# Powersupply.net
KiCad netlist of a schematic drawn in Altium Designer
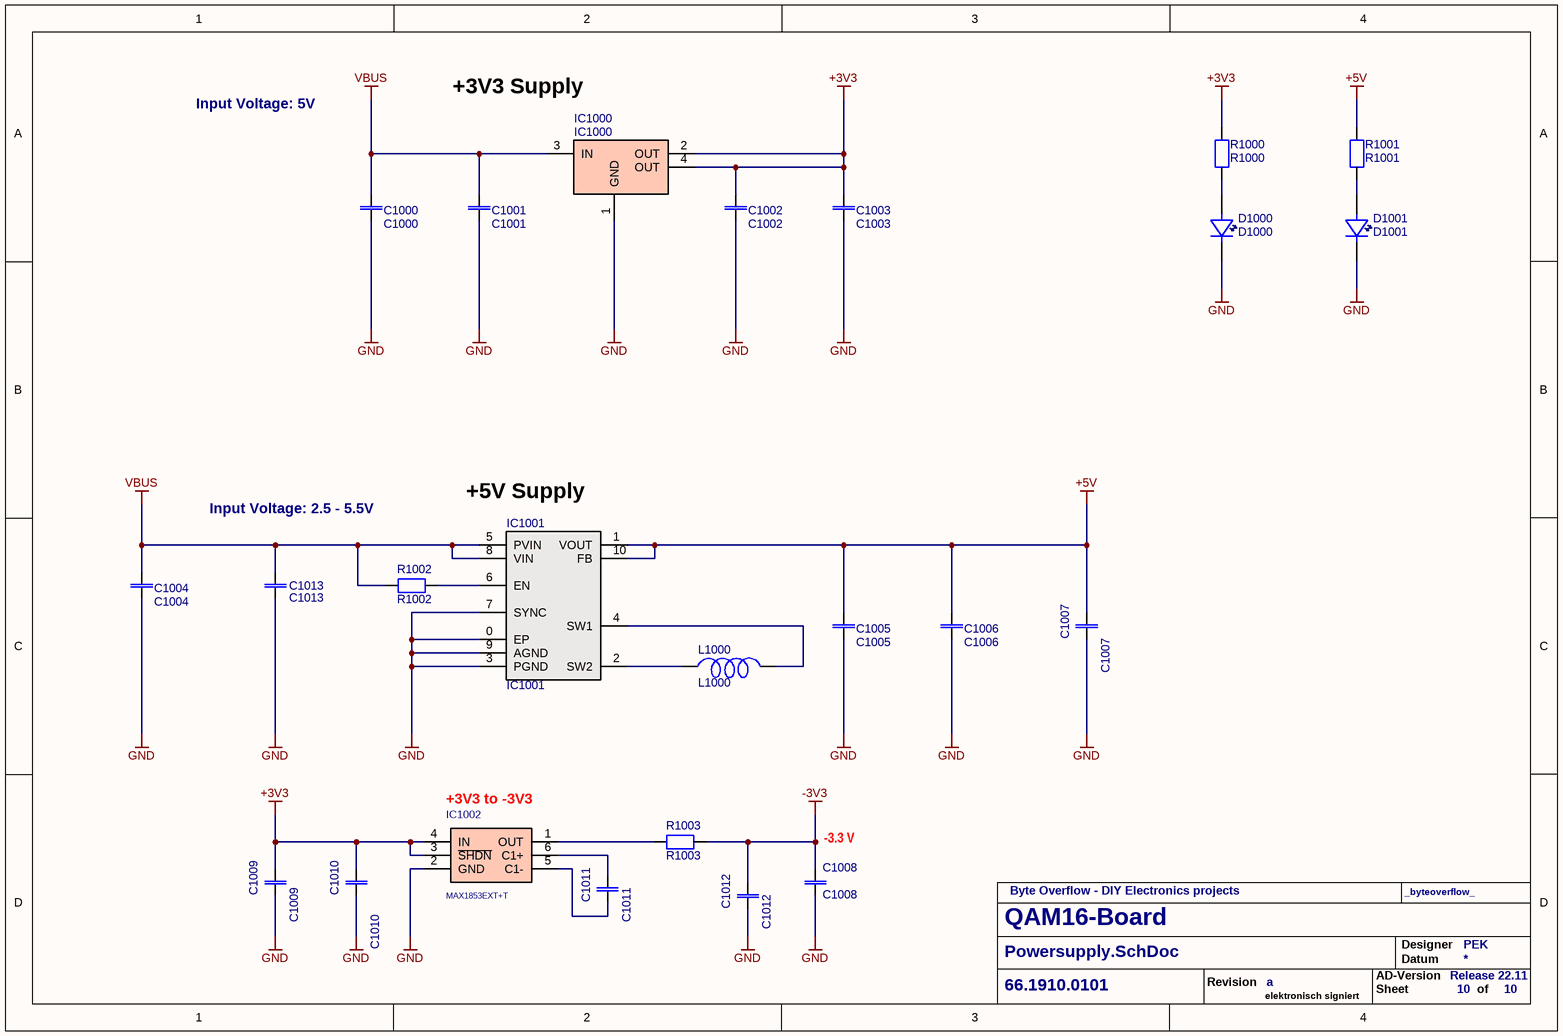
[diagram p0: Powersupply.SchDoc]

(export (version "E")
  (design (tool "Eeschema 10.0.6"))
  (components
    (comp (ref "C1000")
      (value "C 1uF 50V")
      (footprint "0805-2012")
      (description "Capacitor")
      (fields
        (field (name "MANUFACTURER") "Murata Electronics North America")
        (field (name "MANUFACTURER PART NUMBER") "GRM21BF51H105ZA12L")
      )
      (libsource (lib "Database_Libs1") (part "Kondensator"))
    )
    (comp (ref "C1001")
      (value "C 0.1uF 50V")
      (footprint "0805-2012")
      (description "Capacitor")
      (fields
        (field (name "MANUFACTURER") "KEMET")
        (field (name "MANUFACTURER PART NUMBER") "C0805C104K5RACTU")
        (field (name "VERIFICATION") "05.07.2012 OPT")
      )
      (libsource (lib "Database_Libs1") (part "Kondensator"))
    )
    (comp (ref "C1002")
      (value "C 1uF 50V")
      (footprint "0805-2012")
      (description "Capacitor")
      (fields
        (field (name "MANUFACTURER") "Murata Electronics North America")
        (field (name "MANUFACTURER PART NUMBER") "GRM21BF51H105ZA12L")
      )
      (libsource (lib "Database_Libs1") (part "Kondensator"))
    )
    (comp (ref "C1003")
      (value "C 0.1uF 50V")
      (footprint "0805-2012")
      (description "Capacitor")
      (fields
        (field (name "MANUFACTURER") "KEMET")
        (field (name "MANUFACTURER PART NUMBER") "C0805C104K5RACTU")
        (field (name "VERIFICATION") "05.07.2012 OPT")
      )
      (libsource (lib "Database_Libs1") (part "Kondensator"))
    )
    (comp (ref "C1004")
      (value "C 10uF 16V")
      (footprint "0805-2012")
      (description "Capacitor")
      (fields
        (field (name "MANUFACTURER") "AVX Corporation")
        (field (name "MANUFACTURER PART NUMBER") "0805YD106KAT2A")
        (field (name "VERIFICATION") "05.07.2012 OPT")
      )
      (libsource (lib "Database_Libs1") (part "Kondensator"))
    )
    (comp (ref "C1005")
      (value "C 10uF 16V")
      (footprint "0805-2012")
      (description "Capacitor")
      (fields
        (field (name "MANUFACTURER") "AVX Corporation")
        (field (name "MANUFACTURER PART NUMBER") "0805YD106KAT2A")
        (field (name "VERIFICATION") "05.07.2012 OPT")
      )
      (libsource (lib "Database_Libs1") (part "Kondensator"))
    )
    (comp (ref "C1006")
      (value "C 10uF 16V")
      (footprint "0805-2012")
      (description "Capacitor")
      (fields
        (field (name "MANUFACTURER") "AVX Corporation")
        (field (name "MANUFACTURER PART NUMBER") "0805YD106KAT2A")
        (field (name "VERIFICATION") "05.07.2012 OPT")
      )
      (libsource (lib "Database_Libs1") (part "Kondensator"))
    )
    (comp (ref "C1007")
      (value "C 0.1uF 50V")
      (footprint "0805-2012")
      (description "Capacitor")
      (fields
        (field (name "MANUFACTURER") "KEMET")
        (field (name "MANUFACTURER PART NUMBER") "C0805C104K5RACTU")
        (field (name "VERIFICATION") "05.07.2012 OPT")
      )
      (libsource (lib "Database_Libs1") (part "Kondensator"))
    )
    (comp (ref "C1008")
      (value "C 0.1uF 50V")
      (footprint "0805-2012")
      (description "Capacitor")
      (fields
        (field (name "MANUFACTURER") "KEMET")
        (field (name "MANUFACTURER PART NUMBER") "C0805C104K5RACTU")
        (field (name "VERIFICATION") "05.07.2012 OPT")
      )
      (libsource (lib "Database_Libs1") (part "Kondensator"))
    )
    (comp (ref "C1009")
      (value "C 2.2uF 6.3V")
      (footprint "0402-1005")
      (description "Capacitor")
      (fields
        (field (name "MANUFACTURER") "Johanson Dielectrics Inc.")
        (field (name "MANUFACTURER PART NUMBER") "6R3R07X225MV4T")
      )
      (libsource (lib "Database_Libs1") (part "Kondensator"))
    )
    (comp (ref "C1010")
      (value "C 0.1uF 50V")
      (footprint "0805-2012")
      (description "Capacitor")
      (fields
        (field (name "MANUFACTURER") "KEMET")
        (field (name "MANUFACTURER PART NUMBER") "C0805C104K5RACTU")
        (field (name "VERIFICATION") "05.07.2012 OPT")
      )
      (libsource (lib "Database_Libs1") (part "Kondensator"))
    )
    (comp (ref "C1011")
      (value "C 1uF 6.3V")
      (footprint "0402-1005")
      (description "Capacitor")
      (fields
        (field (name "MANUFACTURER") "KEMET")
        (field (name "MANUFACTURER PART NUMBER") "C0402C105K9PACTU")
        (field (name "VERIFICATION") "05.07.2012 OPT")
      )
      (libsource (lib "Database_Libs1") (part "Kondensator"))
    )
    (comp (ref "C1012")
      (value "C 2.2uF 6.3V")
      (footprint "0402-1005")
      (description "Capacitor")
      (fields
        (field (name "MANUFACTURER") "Johanson Dielectrics Inc.")
        (field (name "MANUFACTURER PART NUMBER") "6R3R07X225MV4T")
      )
      (libsource (lib "Database_Libs1") (part "Kondensator"))
    )
    (comp (ref "C1013")
      (value "C 0.1uF 50V")
      (footprint "0805-2012")
      (description "Capacitor")
      (fields
        (field (name "MANUFACTURER") "KEMET")
        (field (name "MANUFACTURER PART NUMBER") "C0805C104K5RACTU")
        (field (name "VERIFICATION") "05.07.2012 OPT")
      )
      (libsource (lib "Database_Libs1") (part "Kondensator"))
    )
    (comp (ref "D1000")
      (value "LED SMD 0805")
      (footprint "0805_LED")
      (description "LED")
      (fields
        (field (name "MANUFACTURER") "Dialight")
        (field (name "MANUFACTURER PART NUMBER") "5988170107F")
        (field (name "VERIFICATION") "25.01.2013 MLP")
      )
      (libsource (lib "Database_Libs1") (part "LED"))
    )
    (comp (ref "D1001")
      (value "LED SMD 0805")
      (footprint "0805_LED")
      (description "LED")
      (fields
        (field (name "MANUFACTURER") "Dialight")
        (field (name "MANUFACTURER PART NUMBER") "5988170107F")
        (field (name "VERIFICATION") "25.01.2013 MLP")
      )
      (libsource (lib "Database_Libs1") (part "LED"))
    )
    (comp (ref "IC1000")
      (value "TLV1117LV33DCY")
      (footprint "SOT-223")
      (description "Voltage regulator")
      (fields
        (field (name "MANUFACTURER") "Texas Instruments")
        (field (name "MANUFACTURER PART NUMBER") "TLV1117LV33DCYR")
      )
      (libsource (lib "Database_Libs1") (part "TLV1117LV"))
    )
    (comp (ref "IC1001")
      (value "ADP2503ACPZ-5.0-R7")
      (footprint "SON10")
      (description "Voltage regulator")
      (fields
        (field (name "MANUFACTURER") "Analog Devices")
        (field (name "MANUFACTURER PART NUMBER") "584-ADP2503ACPZ5.0R7")
      )
      (libsource (lib "Database_Libs1") (part "ADP2503ACPZ-R7"))
    )
    (comp (ref "IC1002")
      (value "MAX1853EXT+T")
      (footprint "SC70-6")
      (description "Voltage regulator")
      (fields (field (name "MANUFACTURER") "Maxim Integrated"))
      (libsource (lib "Database_Libs1") (part "MAX1853"))
    )
    (comp (ref "L1000")
      (value "L 1.5uH 0.5A")
      (footprint "0805-2012")
      (description "Inductor")
      (fields
        (field (name "MANUFACTURER") "TDK")
        (field (name "MANUFACTURER PART NUMBER") "ADL2012-1R5M-T01")
      )
      (libsource (lib "Database_Libs1") (part "Spule"))
    )
    (comp (ref "R1000")
      (value "R 560E 1%")
      (footprint "0805-2012")
      (description "Resistor")
      (fields
        (field (name "MANUFACTURER") "Panasonic Electronic Components")
        (field (name "MANUFACTURER PART NUMBER") "ERJ-6ENF5600V")
      )
      (libsource (lib "Database_Libs1") (part "Resistor"))
    )
    (comp (ref "R1001")
      (value "R 560E 1%")
      (footprint "0805-2012")
      (description "Resistor")
      (fields
        (field (name "MANUFACTURER") "Panasonic Electronic Components")
        (field (name "MANUFACTURER PART NUMBER") "ERJ-6ENF5600V")
      )
      (libsource (lib "Database_Libs1") (part "Resistor"))
    )
    (comp (ref "R1002")
      (value "R 0E 1%")
      (footprint "0805-2012")
      (description "Resistor")
      (fields
        (field (name "MANUFACTURER") "Vishay Dale")
        (field (name "MANUFACTURER PART NUMBER") "CRCW08050000Z0EAHP")
        (field (name "VERIFICATION") "05.03.2013 ENP")
      )
      (libsource (lib "Database_Libs1") (part "Resistor"))
    )
    (comp (ref "R1003")
      (value "R 10E 1%")
      (footprint "0603-1608")
      (description "Resistor")
      (fields
        (field (name "MANUFACTURER") "Vishay Dale")
        (field (name "MANUFACTURER PART NUMBER") "CRCW060310R0FKEA")
        (field (name "VERIFICATION") "26.09.2016 ENP")
      )
      (libsource (lib "Database_Libs1") (part "Resistor"))
    )
  )
  (nets
    (net (code "1") (name "+3V3") (class "Default")
      (node (ref "C1002") (pin "1") (pinfunction "1_1") (pintype "passive"))
      (node (ref "C1003") (pin "1") (pinfunction "1_1") (pintype "passive"))
      (node (ref "C1009") (pin "1") (pinfunction "1_1") (pintype "passive"))
      (node (ref "C1010") (pin "1") (pinfunction "1_1") (pintype "passive"))
      (node (ref "IC1000") (pin "2") (pinfunction "OUT_2") (pintype "power_in"))
      (node (ref "IC1000") (pin "4") (pinfunction "OUT_4") (pintype "passive"))
      (node (ref "IC1002") (pin "3") (pinfunction "~{SHDN}_3") (pintype "passive"))
      (node (ref "IC1002") (pin "4") (pinfunction "IN_4") (pintype "passive"))
      (node (ref "R1000") (pin "1") (pinfunction "1_1") (pintype "passive"))
    )
    (net (code "2") (name "+5V") (class "Default")
      (node (ref "C1005") (pin "1") (pinfunction "1_1") (pintype "passive"))
      (node (ref "C1006") (pin "1") (pinfunction "1_1") (pintype "passive"))
      (node (ref "C1007") (pin "1") (pinfunction "1_1") (pintype "passive"))
      (node (ref "IC1001") (pin "1") (pinfunction "VOUT_1") (pintype "power_in"))
      (node (ref "IC1001") (pin "10") (pinfunction "FB_10") (pintype "power_in"))
      (node (ref "R1001") (pin "1") (pinfunction "1_1") (pintype "passive"))
    )
    (net (code "3") (name "-3V3") (class "Default")
      (node (ref "C1008") (pin "1") (pinfunction "1_1") (pintype "passive"))
      (node (ref "C1012") (pin "1") (pinfunction "1_1") (pintype "passive"))
      (node (ref "R1003") (pin "2") (pinfunction "2_2") (pintype "passive"))
    )
    (net (code "4") (name "GND") (class "Default")
      (node (ref "C1000") (pin "2") (pinfunction "2_2") (pintype "passive"))
      (node (ref "C1001") (pin "2") (pinfunction "2_2") (pintype "passive"))
      (node (ref "C1002") (pin "2") (pinfunction "2_2") (pintype "passive"))
      (node (ref "C1003") (pin "2") (pinfunction "2_2") (pintype "passive"))
      (node (ref "C1004") (pin "2") (pinfunction "2_2") (pintype "passive"))
      (node (ref "C1005") (pin "2") (pinfunction "2_2") (pintype "passive"))
      (node (ref "C1006") (pin "2") (pinfunction "2_2") (pintype "passive"))
      (node (ref "C1007") (pin "2") (pinfunction "2_2") (pintype "passive"))
      (node (ref "C1008") (pin "2") (pinfunction "2_2") (pintype "passive"))
      (node (ref "C1009") (pin "2") (pinfunction "2_2") (pintype "passive"))
      (node (ref "C1010") (pin "2") (pinfunction "2_2") (pintype "passive"))
      (node (ref "C1012") (pin "2") (pinfunction "2_2") (pintype "passive"))
      (node (ref "C1013") (pin "2") (pinfunction "2_2") (pintype "passive"))
      (node (ref "D1000") (pin "2") (pinfunction "K_2") (pintype "passive"))
      (node (ref "D1001") (pin "2") (pinfunction "K_2") (pintype "passive"))
      (node (ref "IC1000") (pin "1") (pinfunction "GND_1") (pintype "power_in"))
      (node (ref "IC1001") (pin "0") (pinfunction "EP_0") (pintype "passive"))
      (node (ref "IC1001") (pin "3") (pinfunction "PGND_3") (pintype "passive"))
      (node (ref "IC1001") (pin "7") (pinfunction "SYNC_7") (pintype "passive"))
      (node (ref "IC1001") (pin "9") (pinfunction "AGND_9") (pintype "passive"))
      (node (ref "IC1002") (pin "2") (pinfunction "GND_2") (pintype "passive"))
    )
    (net (code "5") (name "Net-(D1000-A)") (class "Default")
      (node (ref "D1000") (pin "1") (pinfunction "A_1") (pintype "passive"))
      (node (ref "R1000") (pin "2") (pinfunction "2_2") (pintype "passive"))
    )
    (net (code "6") (name "Net-(D1001-A)") (class "Default")
      (node (ref "D1001") (pin "1") (pinfunction "A_1") (pintype "passive"))
      (node (ref "R1001") (pin "2") (pinfunction "2_2") (pintype "passive"))
    )
    (net (code "7") (name "Net-(IC1001-EN)") (class "Default")
      (node (ref "IC1001") (pin "6") (pinfunction "EN_6") (pintype "passive"))
      (node (ref "R1002") (pin "2") (pinfunction "2_2") (pintype "passive"))
    )
    (net (code "8") (name "Net-(IC1001-SW1)") (class "Default")
      (node (ref "IC1001") (pin "4") (pinfunction "SW1_4") (pintype "passive"))
      (node (ref "L1000") (pin "2") (pintype "passive"))
    )
    (net (code "9") (name "Net-(IC1001-SW2)") (class "Default")
      (node (ref "IC1001") (pin "2") (pinfunction "SW2_2") (pintype "passive"))
      (node (ref "L1000") (pin "1") (pintype "passive"))
    )
    (net (code "10") (name "Net-(IC1002-C1+)") (class "Default")
      (node (ref "C1011") (pin "1") (pinfunction "1_1") (pintype "passive"))
      (node (ref "IC1002") (pin "6") (pinfunction "C1+_6") (pintype "passive"))
    )
    (net (code "11") (name "Net-(IC1002-C1-)") (class "Default")
      (node (ref "C1011") (pin "2") (pinfunction "2_2") (pintype "passive"))
      (node (ref "IC1002") (pin "5") (pinfunction "C1-_5") (pintype "passive"))
    )
    (net (code "12") (name "Net-(IC1002-OUT)") (class "Default")
      (node (ref "IC1002") (pin "1") (pinfunction "OUT_1") (pintype "passive"))
      (node (ref "R1003") (pin "1") (pinfunction "1_1") (pintype "passive"))
    )
    (net (code "13") (name "VBUS") (class "Default")
      (node (ref "C1000") (pin "1") (pinfunction "1_1") (pintype "passive"))
      (node (ref "C1001") (pin "1") (pinfunction "1_1") (pintype "passive"))
      (node (ref "C1004") (pin "1") (pinfunction "1_1") (pintype "passive"))
      (node (ref "C1013") (pin "1") (pinfunction "1_1") (pintype "passive"))
      (node (ref "IC1000") (pin "3") (pinfunction "IN_3") (pintype "passive"))
      (node (ref "IC1001") (pin "5") (pinfunction "PVIN_5") (pintype "passive"))
      (node (ref "IC1001") (pin "8") (pinfunction "VIN_8") (pintype "power_in"))
      (node (ref "R1002") (pin "1") (pinfunction "1_1") (pintype "passive"))
    )
  )
)
